# lm8039-sx1276-atmel328p-v0_1.net
KiCad netlist of a schematic drawn in EAGLE
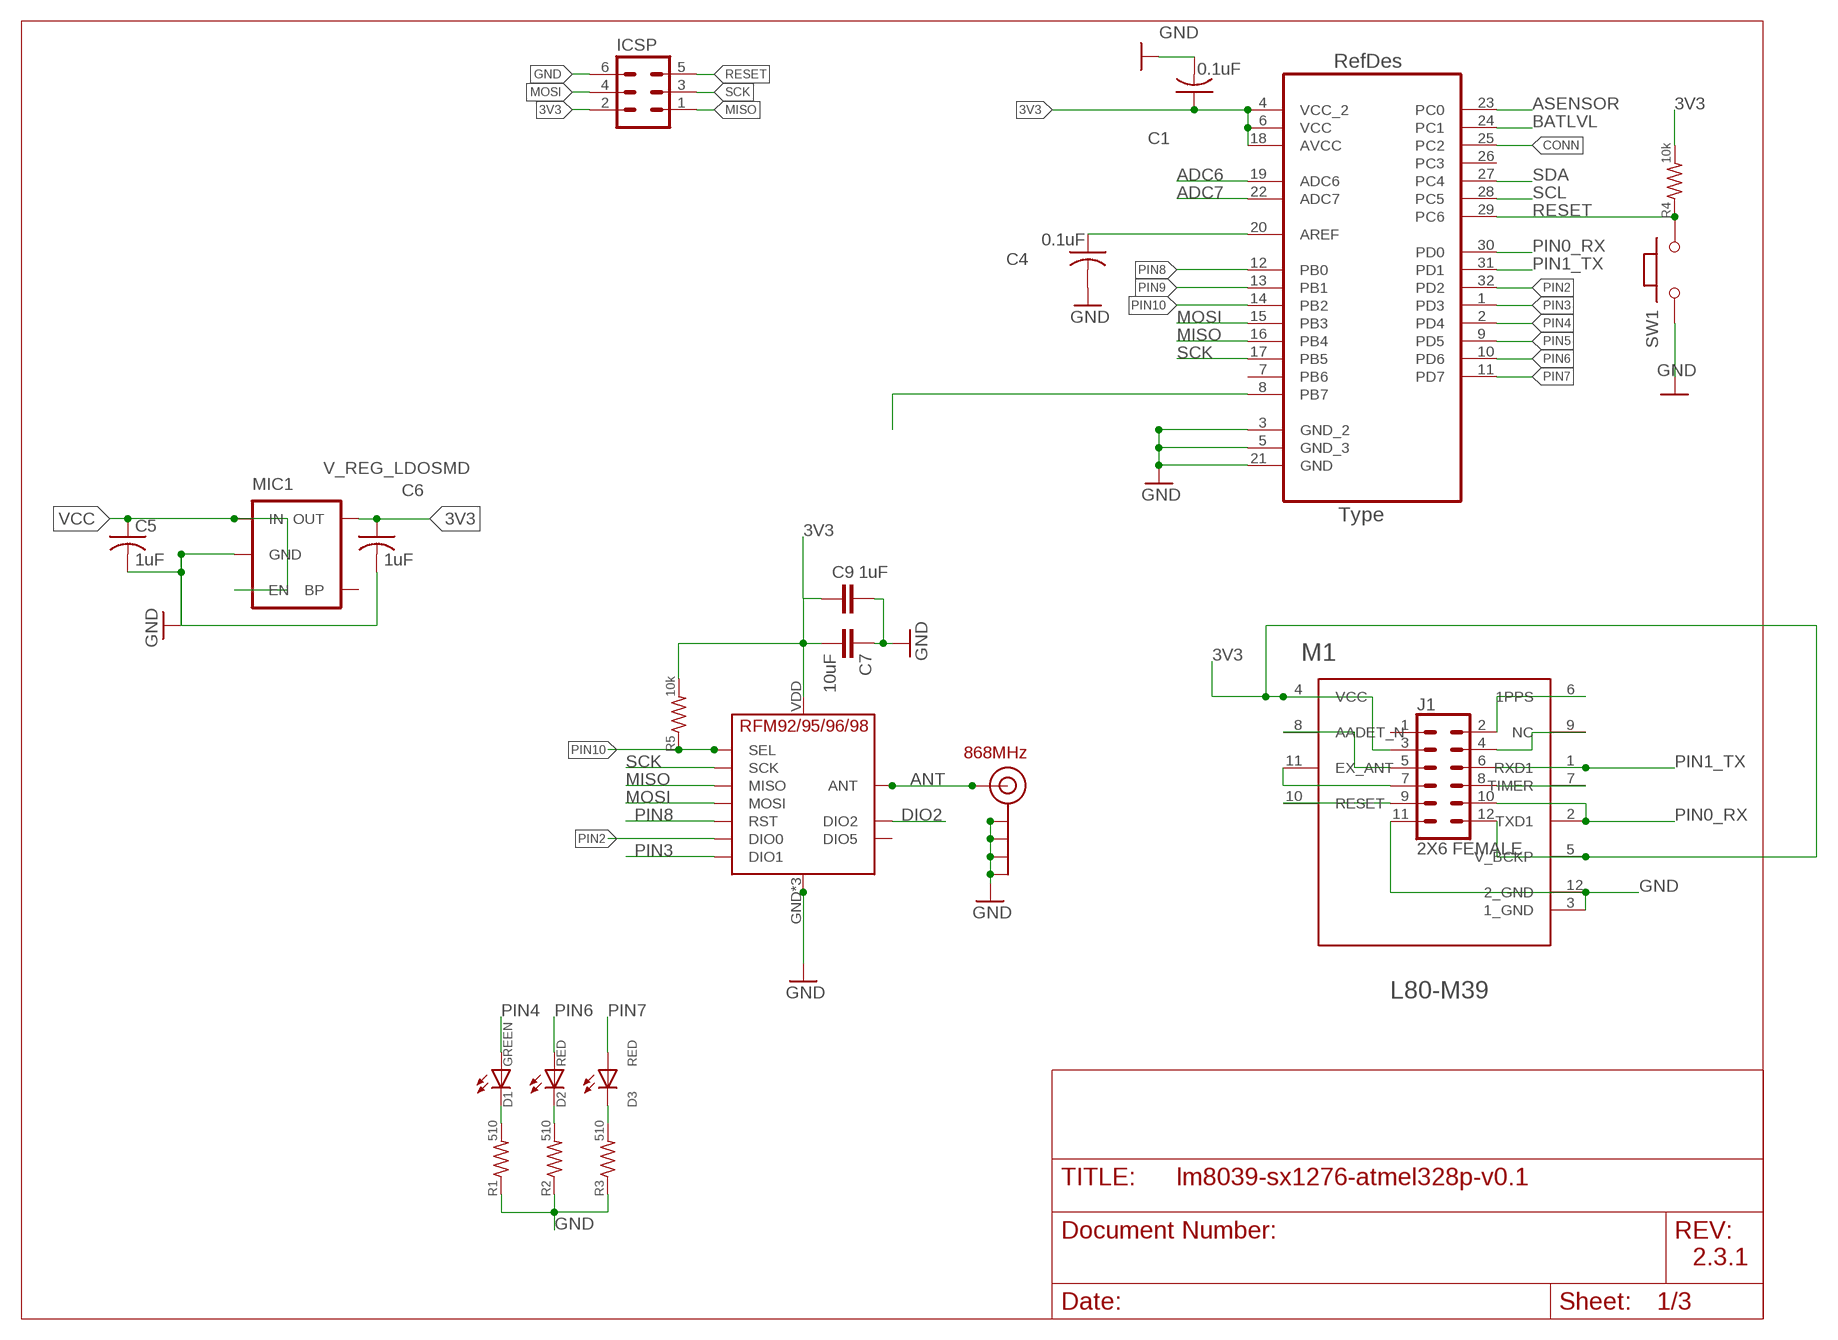
[diagram p0: schematic, sheet 1]
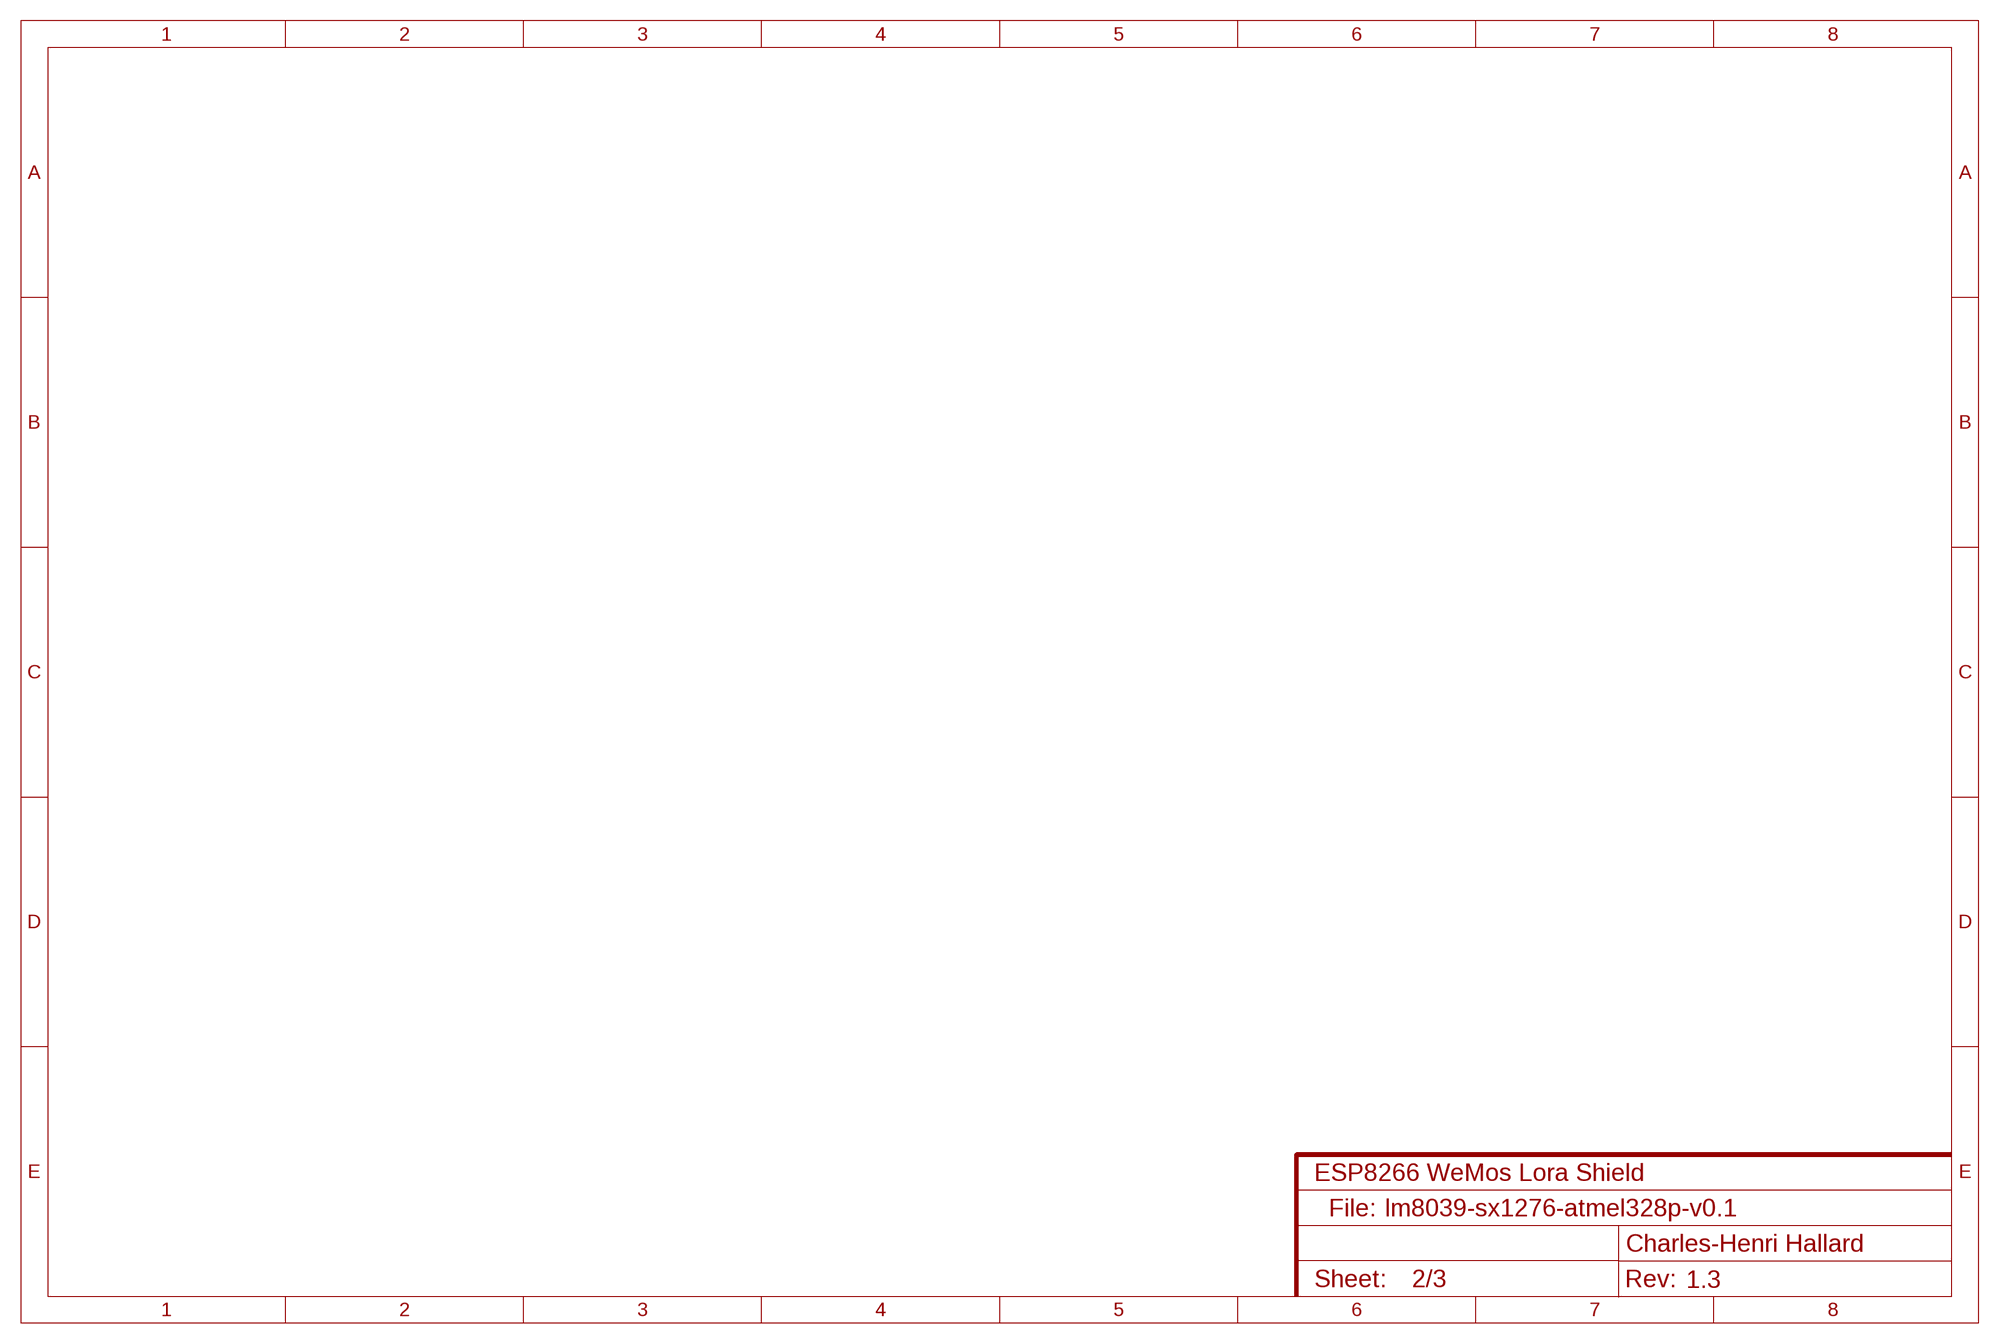
[diagram p1: schematic, sheet 2]

(export (version "E")
  (design (tool "Eeschema 10.0.6"))
  (components
    (comp (ref "C1")
      (value "0.1uF")
      (footprint "eagle-import:C0805")
      (libsource (lib "eagle-import") (part "C-USC0805"))
    )
    (comp (ref "C4")
      (value "0.1uF")
      (footprint "eagle-import:C0805")
      (libsource (lib "eagle-import") (part "C-USC0805"))
    )
    (comp (ref "C5")
      (value "1uF")
      (footprint "eagle-import:C0805")
      (libsource (lib "eagle-import") (part "C-USC0805"))
    )
    (comp (ref "C6")
      (value "1uF")
      (footprint "eagle-import:C0805")
      (libsource (lib "eagle-import") (part "C-USC0805"))
    )
    (comp (ref "C7")
      (value "10uF")
      (footprint "eagle-import:0805-CAP-LARGEPADS")
      (libsource (lib "eagle-import") (part "CAP0805-CAP-LARGEPADS"))
    )
    (comp (ref "C9")
      (value "1uF")
      (footprint "eagle-import:0805-CAP-LARGEPADS")
      (libsource (lib "eagle-import") (part "CAP0805-CAP-LARGEPADS"))
    )
    (comp (ref "D1")
      (value "GREEN")
      (footprint "eagle-import:LED0603")
      (libsource (lib "eagle-import") (part "LED-0603"))
    )
    (comp (ref "D2")
      (value "RED")
      (footprint "eagle-import:LED0603")
      (libsource (lib "eagle-import") (part "LED-0603"))
    )
    (comp (ref "D3")
      (value "RED")
      (footprint "eagle-import:LED0603")
      (libsource (lib "eagle-import") (part "LED-0603"))
    )
    (comp (ref "ICSP")
      (value "MA03-2")
      (footprint "eagle-import:MA03-2")
      (libsource (lib "eagle-import") (part "MA03-2"))
    )
    (comp (ref "J$2")
      (value "ANTENNATINY")
      (footprint "eagle-import:SMA_UFL_PAD_TINY")
      (libsource (lib "eagle-import") (part "ANTENNATINY"))
    )
    (comp (ref "J1")
      (value "2X6 FEMALE")
      (footprint "eagle-import:2X6")
      (libsource (lib "eagle-import") (part "CONN_06X2PTH_FEMALE"))
    )
    (comp (ref "M1")
      (value "QUECTEL_L80-M39QUECTEL_L80-M39_0_0")
      (footprint "eagle-import:QUECTEL_L80-M39_0")
      (fields (field (name "MF") "Quectel") (field (name "MPN") "L80-M39"))
      (libsource (lib "eagle-import") (part "QUECTEL_L80-M39QUECTEL_L80-M39_0_0"))
    )
    (comp (ref "MIC1")
      (value "V_REG_LDOSMD")
      (footprint "eagle-import:SOT23-5")
      (libsource (lib "eagle-import") (part "V_REG_LDOSMD"))
    )
    (comp (ref "R1")
      (value "510")
      (footprint "eagle-import:R0603")
      (libsource (lib "eagle-import") (part "R-US_R0603"))
    )
    (comp (ref "R2")
      (value "510")
      (footprint "eagle-import:R0603")
      (libsource (lib "eagle-import") (part "R-US_R0603"))
    )
    (comp (ref "R3")
      (value "510")
      (footprint "eagle-import:R0603")
      (libsource (lib "eagle-import") (part "R-US_R0603"))
    )
    (comp (ref "R4")
      (value "10k")
      (footprint "eagle-import:R0603")
      (libsource (lib "eagle-import") (part "R-US_R0603"))
    )
    (comp (ref "R5")
      (value "10k")
      (footprint "eagle-import:R0603")
      (libsource (lib "eagle-import") (part "R-US_R0603"))
    )
    (comp (ref "SW1")
      (value "RESET")
      (footprint "eagle-import:SMD_157SW")
      (libsource (lib "eagle-import") (part "MYSMD_PB157"))
    )
    (comp (ref "U$5")
      (value "RFM95")
      (footprint "eagle-import:RFM95")
      (libsource (lib "eagle-import") (part "RFM95"))
    )
    (comp (ref "U1")
      (value "ATMEGA328P-AU")
      (footprint "eagle-import:QFP80P900X900X120-32N")
      (libsource (lib "eagle-import") (part "ATMEGA328P-AU"))
    )
  )
  (nets
    (net (code "1") (name "3V3") (class "Default")
      (node (ref "C1") (pin "1") (pinfunction "1_1") (pintype "passive"))
      (node (ref "C6") (pin "1") (pinfunction "1_1") (pintype "passive"))
      (node (ref "C7") (pin "2") (pinfunction "2_2") (pintype "passive"))
      (node (ref "C9") (pin "2") (pinfunction "2_2") (pintype "passive"))
      (node (ref "ICSP") (pin "2") (pinfunction "2_2") (pintype "passive"))
      (node (ref "J1") (pin "12") (pinfunction "12_12") (pintype "passive"))
      (node (ref "J1") (pin "3") (pinfunction "3_3") (pintype "passive"))
      (node (ref "M1") (pin "4") (pinfunction "VCC_4") (pintype "power_in"))
      (node (ref "M1") (pin "5") (pinfunction "V_BCKP_5") (pintype "power_in"))
      (node (ref "MIC1") (pin "5") (pinfunction "OUT_5") (pintype "passive"))
      (node (ref "R4") (pin "2") (pinfunction "2_2") (pintype "passive"))
      (node (ref "R5") (pin "2") (pinfunction "2_2") (pintype "passive"))
      (node (ref "U$5") (pin "VDD") (pinfunction "VCC_VDD") (pintype "power_in"))
      (node (ref "U1") (pin "18") (pinfunction "AVCC_18") (pintype "power_in"))
      (node (ref "U1") (pin "4") (pinfunction "VCC_2_4") (pintype "power_in"))
      (node (ref "U1") (pin "6") (pinfunction "VCC_6") (pintype "power_in"))
    )
    (net (code "2") (name "ADC6") (class "Default")
      (node (ref "U1") (pin "19") (pinfunction "ADC6_19") (pintype "input"))
    )
    (net (code "3") (name "ADC7") (class "Default")
      (node (ref "U1") (pin "22") (pinfunction "ADC7_22") (pintype "input"))
    )
    (net (code "4") (name "ANT") (class "Default")
      (node (ref "J$2") (pin "ANT1") (pinfunction "SIGNAL_ANT1") (pintype "bidirectional"))
      (node (ref "J$2") (pin "ANT2") (pinfunction "SIGNAL_ANT2") (pintype "bidirectional"))
      (node (ref "J$2") (pin "ANT3") (pinfunction "SIGNAL_ANT3") (pintype "bidirectional"))
      (node (ref "U$5") (pin "ANT") (pinfunction "ANT_ANT") (pintype "passive"))
    )
    (net (code "5") (name "ASENSOR") (class "Default")
      (node (ref "U1") (pin "23") (pinfunction "PC0_23") (pintype "bidirectional"))
    )
    (net (code "6") (name "BATLVL") (class "Default")
      (node (ref "U1") (pin "24") (pinfunction "PC1_24") (pintype "bidirectional"))
    )
    (net (code "7") (name "CONN") (class "Default")
      (node (ref "U1") (pin "25") (pinfunction "PC2_25") (pintype "bidirectional"))
    )
    (net (code "8") (name "DIO2") (class "Default")
      (node (ref "U$5") (pin "DIO2") (pinfunction "DIO2_DIO2") (pintype "open_collector"))
    )
    (net (code "9") (name "GND") (class "Default")
      (node (ref "C1") (pin "2") (pinfunction "2_2") (pintype "passive"))
      (node (ref "C4") (pin "2") (pinfunction "2_2") (pintype "passive"))
      (node (ref "C5") (pin "2") (pinfunction "2_2") (pintype "passive"))
      (node (ref "C6") (pin "2") (pinfunction "2_2") (pintype "passive"))
      (node (ref "C7") (pin "1") (pinfunction "1_1") (pintype "passive"))
      (node (ref "C9") (pin "1") (pinfunction "1_1") (pintype "passive"))
      (node (ref "ICSP") (pin "6") (pinfunction "6_6") (pintype "passive"))
      (node (ref "J$2") (pin "GND1") (pinfunction "GND_GND1") (pintype "bidirectional"))
      (node (ref "J$2") (pin "GND2") (pinfunction "GND_GND2") (pintype "bidirectional"))
      (node (ref "J$2") (pin "GND3") (pinfunction "GND_GND3") (pintype "bidirectional"))
      (node (ref "J$2") (pin "GND4") (pinfunction "GND_GND4") (pintype "bidirectional"))
      (node (ref "J1") (pin "11") (pinfunction "11_11") (pintype "passive"))
      (node (ref "M1") (pin "12") (pinfunction "2_GND_12") (pintype "power_in"))
      (node (ref "M1") (pin "3") (pinfunction "1_GND_3") (pintype "power_in"))
      (node (ref "MIC1") (pin "2") (pinfunction "GND_2") (pintype "input"))
      (node (ref "R1") (pin "1") (pinfunction "1_1") (pintype "passive"))
      (node (ref "R2") (pin "1") (pinfunction "1_1") (pintype "passive"))
      (node (ref "R3") (pin "1") (pinfunction "1_1") (pintype "passive"))
      (node (ref "SW1") (pin "1") (pinfunction "1_1") (pintype "passive"))
      (node (ref "U$5") (pin "GND") (pinfunction "GND_GND") (pintype "power_in"))
      (node (ref "U$5") (pin "GND1") (pinfunction "GND_GND1") (pintype "power_in"))
      (node (ref "U$5") (pin "GND2") (pinfunction "GND_GND2") (pintype "power_in"))
      (node (ref "U1") (pin "21") (pinfunction "GND_21") (pintype "passive"))
      (node (ref "U1") (pin "3") (pinfunction "GND_2_3") (pintype "passive"))
      (node (ref "U1") (pin "5") (pinfunction "GND_3_5") (pintype "passive"))
    )
    (net (code "10") (name "MISO") (class "Default")
      (node (ref "ICSP") (pin "1") (pinfunction "1_1") (pintype "passive"))
      (node (ref "U$5") (pin "MISO") (pinfunction "MISO_MISO") (pintype "input"))
      (node (ref "U1") (pin "16") (pinfunction "PB4_16") (pintype "bidirectional"))
    )
    (net (code "11") (name "MOSI") (class "Default")
      (node (ref "ICSP") (pin "4") (pinfunction "4_4") (pintype "passive"))
      (node (ref "U$5") (pin "MOSI") (pinfunction "MOSI_MOSI") (pintype "output"))
      (node (ref "U1") (pin "15") (pinfunction "PB3_15") (pintype "bidirectional"))
    )
    (net (code "12") (name "Net-(D1-PadC)") (class "Default")
      (node (ref "D1") (pin "C") (pinfunction "C_C") (pintype "passive"))
      (node (ref "R1") (pin "2") (pinfunction "2_2") (pintype "passive"))
    )
    (net (code "13") (name "Net-(D2-PadC)") (class "Default")
      (node (ref "D2") (pin "C") (pinfunction "C_C") (pintype "passive"))
      (node (ref "R2") (pin "2") (pinfunction "2_2") (pintype "passive"))
    )
    (net (code "14") (name "Net-(D3-PadC)") (class "Default")
      (node (ref "D3") (pin "C") (pinfunction "C_C") (pintype "passive"))
      (node (ref "R3") (pin "2") (pinfunction "2_2") (pintype "passive"))
    )
    (net (code "15") (name "Net-(M1-1PPS)") (class "Default")
      (node (ref "J1") (pin "2") (pinfunction "2_2") (pintype "passive"))
      (node (ref "M1") (pin "6") (pinfunction "1PPS_6") (pintype "output"))
    )
    (net (code "16") (name "Net-(M1-AADET_N)") (class "Default")
      (node (ref "J1") (pin "5") (pinfunction "5_5") (pintype "passive"))
      (node (ref "M1") (pin "8") (pinfunction "AADET_N_8") (pintype "bidirectional"))
    )
    (net (code "17") (name "Net-(M1-EX_ANT)") (class "Default")
      (node (ref "J1") (pin "7") (pinfunction "7_7") (pintype "passive"))
      (node (ref "M1") (pin "11") (pinfunction "EX_ANT_11") (pintype "input"))
    )
    (net (code "18") (name "Net-(M1-NC)") (class "Default")
      (node (ref "J1") (pin "4") (pinfunction "4_4") (pintype "passive"))
      (node (ref "M1") (pin "9") (pinfunction "NC_9") (pintype "passive"))
    )
    (net (code "19") (name "Net-(M1-RESET)") (class "Default")
      (node (ref "J1") (pin "9") (pinfunction "9_9") (pintype "passive"))
      (node (ref "M1") (pin "10") (pinfunction "RESET_10") (pintype "input"))
    )
    (net (code "20") (name "Net-(M1-TIMER)") (class "Default")
      (node (ref "J1") (pin "8") (pinfunction "8_8") (pintype "passive"))
      (node (ref "M1") (pin "7") (pinfunction "TIMER_7") (pintype "output"))
    )
    (net (code "21") (name "Net-(U1-AREF)") (class "Default")
      (node (ref "C4") (pin "1") (pinfunction "1_1") (pintype "passive"))
      (node (ref "U1") (pin "20") (pinfunction "AREF_20") (pintype "input"))
    )
    (net (code "22") (name "PIN0_RX") (class "Default")
      (node (ref "J1") (pin "10") (pinfunction "10_10") (pintype "passive"))
      (node (ref "M1") (pin "2") (pinfunction "TXD1_2") (pintype "output"))
      (node (ref "U1") (pin "30") (pinfunction "PD0_30") (pintype "bidirectional"))
    )
    (net (code "23") (name "PIN1_TX") (class "Default")
      (node (ref "J1") (pin "6") (pinfunction "6_6") (pintype "passive"))
      (node (ref "M1") (pin "1") (pinfunction "RXD1_1") (pintype "input"))
      (node (ref "U1") (pin "31") (pinfunction "PD1_31") (pintype "bidirectional"))
    )
    (net (code "24") (name "PIN2") (class "Default")
      (node (ref "U$5") (pin "DIO0") (pinfunction "DIO0_DIO0") (pintype "open_collector"))
      (node (ref "U1") (pin "32") (pinfunction "PD2_32") (pintype "bidirectional"))
    )
    (net (code "25") (name "PIN3") (class "Default")
      (node (ref "U$5") (pin "DIO1") (pinfunction "DIO1_DIO1") (pintype "open_collector"))
      (node (ref "U1") (pin "1") (pinfunction "PD3_1") (pintype "bidirectional"))
    )
    (net (code "26") (name "PIN4") (class "Default")
      (node (ref "D1") (pin "A") (pinfunction "A_A") (pintype "passive"))
      (node (ref "U1") (pin "2") (pinfunction "PD4_2") (pintype "bidirectional"))
    )
    (net (code "27") (name "PIN5") (class "Default")
      (node (ref "U1") (pin "9") (pinfunction "PD5_9") (pintype "bidirectional"))
    )
    (net (code "28") (name "PIN6") (class "Default")
      (node (ref "D2") (pin "A") (pinfunction "A_A") (pintype "passive"))
      (node (ref "U1") (pin "10") (pinfunction "PD6_10") (pintype "bidirectional"))
    )
    (net (code "29") (name "PIN7") (class "Default")
      (node (ref "D3") (pin "A") (pinfunction "A_A") (pintype "passive"))
      (node (ref "U1") (pin "11") (pinfunction "PD7_11") (pintype "bidirectional"))
    )
    (net (code "30") (name "PIN8") (class "Default")
      (node (ref "U$5") (pin "RST") (pinfunction "RST_RST") (pintype "open_collector"))
      (node (ref "U1") (pin "12") (pinfunction "PB0_12") (pintype "bidirectional"))
    )
    (net (code "31") (name "PIN9") (class "Default")
      (node (ref "U1") (pin "13") (pinfunction "PB1_13") (pintype "bidirectional"))
    )
    (net (code "32") (name "PIN10") (class "Default")
      (node (ref "R5") (pin "1") (pinfunction "1_1") (pintype "passive"))
      (node (ref "U$5") (pin "NSS") (pinfunction "SEL_NSS") (pintype "input"))
      (node (ref "U1") (pin "14") (pinfunction "PB2_14") (pintype "bidirectional"))
    )
    (net (code "33") (name "RESET") (class "Default")
      (node (ref "ICSP") (pin "5") (pinfunction "5_5") (pintype "passive"))
      (node (ref "R4") (pin "1") (pinfunction "1_1") (pintype "passive"))
      (node (ref "SW1") (pin "2") (pinfunction "2_2") (pintype "passive"))
      (node (ref "U1") (pin "29") (pinfunction "PC6_29") (pintype "bidirectional"))
    )
    (net (code "34") (name "SCK") (class "Default")
      (node (ref "ICSP") (pin "3") (pinfunction "3_3") (pintype "passive"))
      (node (ref "U$5") (pin "SCK") (pinfunction "SCK_SCK") (pintype "input"))
      (node (ref "U1") (pin "17") (pinfunction "PB5_17") (pintype "bidirectional"))
    )
    (net (code "35") (name "SCL") (class "Default")
      (node (ref "U1") (pin "28") (pinfunction "PC5_28") (pintype "bidirectional"))
    )
    (net (code "36") (name "SDA") (class "Default")
      (node (ref "U1") (pin "27") (pinfunction "PC4_27") (pintype "bidirectional"))
    )
    (net (code "37") (name "VCC") (class "Default")
      (node (ref "C5") (pin "1") (pinfunction "1_1") (pintype "passive"))
      (node (ref "MIC1") (pin "1") (pinfunction "IN_1") (pintype "input"))
      (node (ref "MIC1") (pin "3") (pinfunction "EN_3") (pintype "input"))
    )
    (net (code "38") (name "unconnected-(J1-Pad1)") (class "Default")
      (node (ref "J1") (pin "1") (pinfunction "1_1") (pintype "passive"))
    )
    (net (code "39") (name "unconnected-(MIC1-BP-Pad4)") (class "Default")
      (node (ref "MIC1") (pin "4") (pinfunction "BP_4") (pintype "input"))
    )
    (net (code "40") (name "unconnected-(U$5-PadDIO5)") (class "Default")
      (node (ref "U$5") (pin "DIO5") (pinfunction "DIO5_DIO5") (pintype "open_collector"))
    )
    (net (code "41") (name "unconnected-(U1-PB6-Pad7)") (class "Default")
      (node (ref "U1") (pin "7") (pinfunction "PB6_7") (pintype "bidirectional"))
    )
    (net (code "42") (name "unconnected-(U1-PB7-Pad8)") (class "Default")
      (node (ref "U1") (pin "8") (pinfunction "PB7_8") (pintype "bidirectional"))
    )
    (net (code "43") (name "unconnected-(U1-PC3-Pad26)") (class "Default")
      (node (ref "U1") (pin "26") (pinfunction "PC3_26") (pintype "bidirectional"))
    )
  )
)
